# Tiny817_Xplained_Pro_current_measurement.net
KiCad netlist of a schematic drawn in Altium Designer
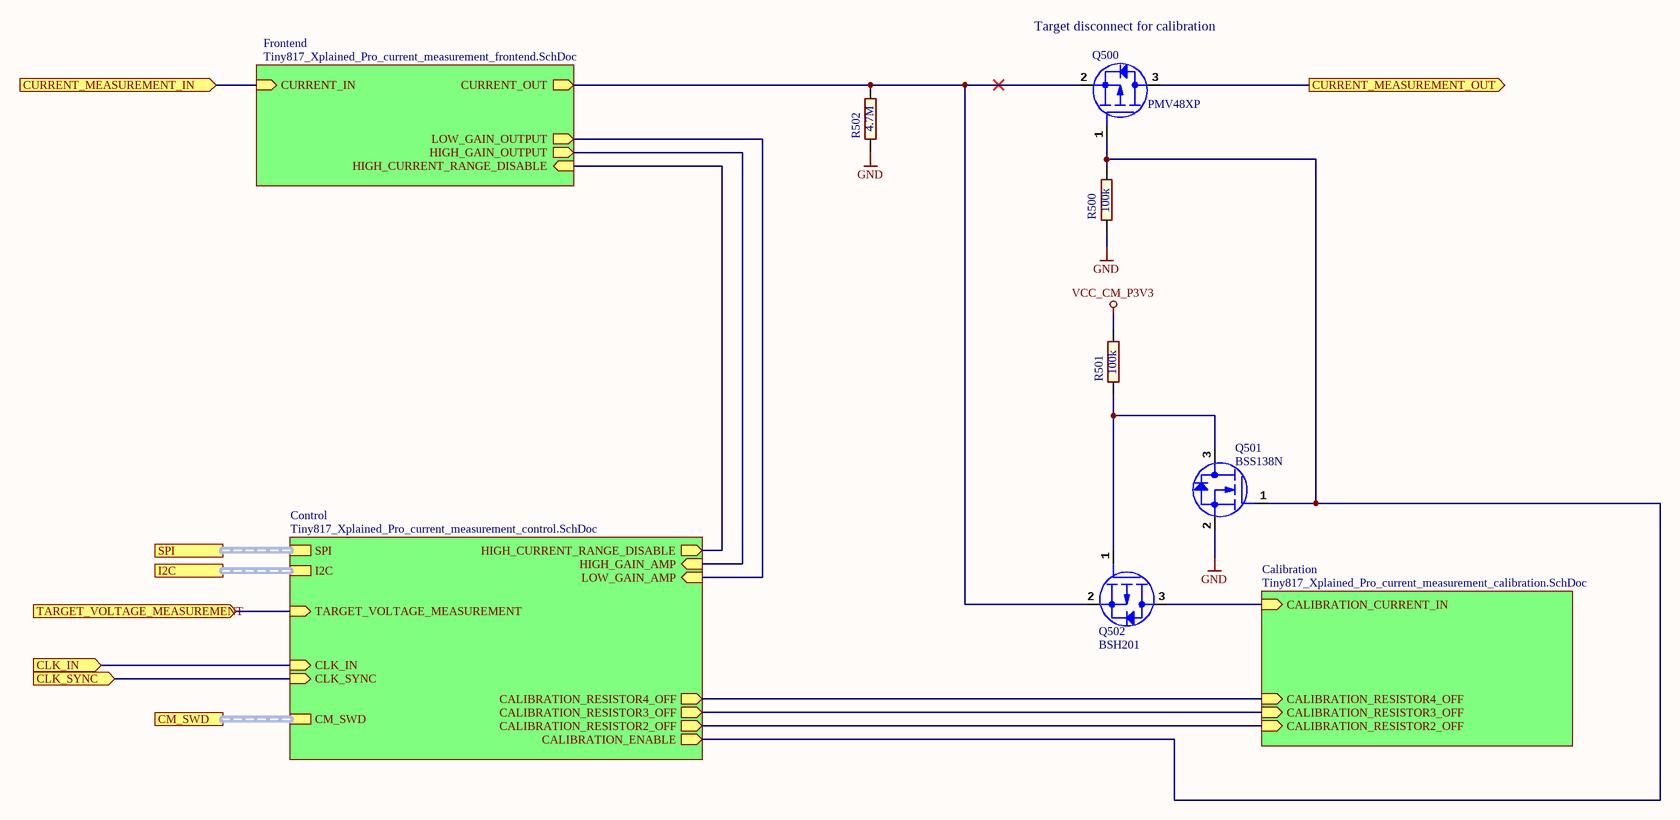
[diagram p0: Tiny817_Xplained_Pro_current_measurement.SchDoc]

(export (version "E")
  (design (tool "Eeschema 10.0.6"))
  (components
    (comp (ref "Q500")
      (value "PMV48XP")
      (footprint "AP5-00002")
      (fields (field (name "MANUFACTURER") "NXP") (field (name "MPN") "PMV48XP,215"))
      (libsource (lib "AltiumDbLib") (part "MOSFET_P_GSD"))
    )
    (comp (ref "Q501")
      (value "BSS138N")
      (footprint "AP5-00002")
      (fields (field (name "MANUFACTURER") "Infineon"))
      (libsource (lib "AltiumDbLib") (part "MOSFET_N_GSD"))
    )
    (comp (ref "Q502")
      (value "BSH201")
      (footprint "AP5-00002")
      (fields (field (name "MANUFACTURER") "NXP") (field (name "MPN") "BSH201,215"))
      (libsource (lib "AltiumDbLib") (part "MOSFET_P_GSD"))
    )
    (comp (ref "R500")
      (value "100k")
      (footprint "AP2-00011")
      (description "Thick film resistor, SMD 0402, 1/16W, 1%")
      (fields (field (name "TOLERANCE") "1 %") (field (name "MANUFACTURER") "ASJ Holdings"))
      (libsource (lib "") (part "R2_1"))
    )
    (comp (ref "R501")
      (value "100k")
      (footprint "AP2-00011")
      (description "Thick film resistor, SMD 0402, 1/16W, 1%")
      (fields (field (name "TOLERANCE") "1 %") (field (name "MANUFACTURER") "ASJ Holdings"))
      (libsource (lib "AltiumDbLib") (part "R2"))
    )
    (comp (ref "R502")
      (value "4.7M")
      (footprint "AP2-00011")
      (description "Thick film SMD 0402 1/16W 1%")
      (fields (field (name "TOLERANCE") "1 %") (field (name "MANUFACTURER") "Yageo"))
      (libsource (lib "") (part "R2_1"))
    )
  )
  (nets
    (net (code "4") (name "/CALIBRATION_CURRENT_IN") (class "Default")
      (node (ref "Q502") (pin "3") (pinfunction "D_3") (pintype "passive"))
    )
    (net (code "5") (name "/CALIBRATION_ENABLE") (class "Default")
      (node (ref "Q500") (pin "1") (pinfunction "G_1") (pintype "passive"))
      (node (ref "Q501") (pin "1") (pinfunction "G_1") (pintype "passive"))
      (node (ref "R500") (pin "2") (pinfunction "2_2") (pintype "passive"))
    )
    (net (code "13") (name "/CURRENT_MEASUREMENT_OUT") (class "Default")
      (node (ref "Q500") (pin "3") (pinfunction "D_3") (pintype "passive"))
    )
    (net (code "14") (name "/CURRENT_OUT") (class "Default")
      (node (ref "Q500") (pin "2") (pinfunction "S_2") (pintype "passive"))
      (node (ref "Q502") (pin "2") (pinfunction "S_2") (pintype "passive"))
      (node (ref "R502") (pin "2") (pinfunction "2_2") (pintype "passive"))
    )
    (net (code "21") (name "GND") (class "Default")
      (node (ref "Q501") (pin "2") (pinfunction "S_2") (pintype "passive"))
      (node (ref "R500") (pin "1") (pinfunction "1_1") (pintype "passive"))
      (node (ref "R502") (pin "1") (pinfunction "1_1") (pintype "passive"))
    )
    (net (code "22") (name "Net-(Q501-D)") (class "Default")
      (node (ref "Q501") (pin "3") (pinfunction "D_3") (pintype "passive"))
      (node (ref "Q502") (pin "1") (pinfunction "G_1") (pintype "passive"))
      (node (ref "R501") (pin "1") (pinfunction "1_1") (pintype "passive"))
    )
    (net (code "23") (name "VCC_CM_P3V3") (class "Default")
      (node (ref "R501") (pin "2") (pinfunction "2_2") (pintype "passive"))
    )
  )
)
